# USB_Communication.net
KiCad netlist of a schematic drawn in Altium Designer
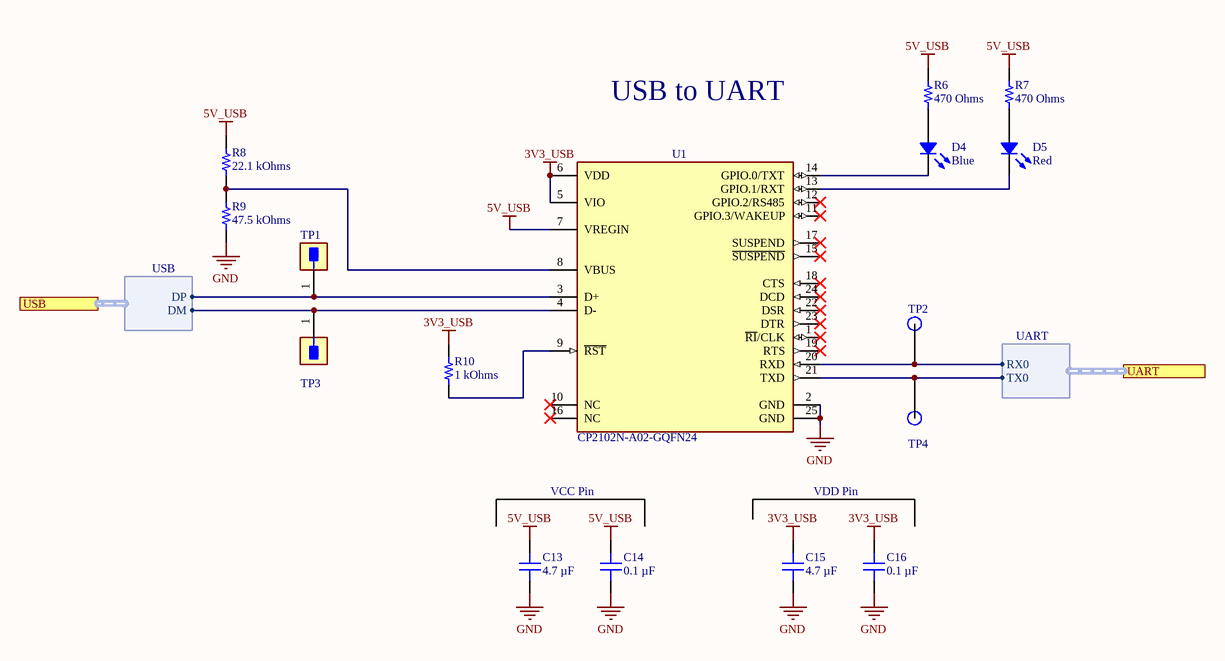
[diagram p0: USB Communication.SchDoc]

(export (version "E")
  (design (tool "Eeschema 10.0.6"))
  (components
    (comp (ref "C13")
      (value "4.7 µF")
      (footprint "CAP 0603_1608")
      (description "CAP CER 4.7UF 10V X5R 0603")
      (fields
        (field (name "PART NUMBER") "CL10A475KP8NNNC")
        (field (name "MANUFACTURER") "Samsung Electro-Mechanics")
      )
      (libsource (lib "Celestial Altium Library - altium_library") (part "Capacitor"))
    )
    (comp (ref "C14")
      (value "0.1 µF")
      (footprint "CAP 0603_1608")
      (description "CAP CER 0.1UF 50V X7R 0603")
      (fields (field (name "PART NUMBER") "C0603C104K5RAC7411") (field (name "MANUFACTURER") "KEMET"))
      (libsource (lib "Celestial Altium Library - altium_library") (part "Capacitor"))
    )
    (comp (ref "C15")
      (value "4.7 µF")
      (footprint "CAP 0603_1608")
      (description "CAP CER 4.7UF 10V X5R 0603")
      (fields
        (field (name "PART NUMBER") "CL10A475KP8NNNC")
        (field (name "MANUFACTURER") "Samsung Electro-Mechanics")
      )
      (libsource (lib "Celestial Altium Library - altium_library") (part "Capacitor"))
    )
    (comp (ref "C16")
      (value "0.1 µF")
      (footprint "CAP 0603_1608")
      (description "CAP CER 0.1UF 50V X7R 0603")
      (fields (field (name "PART NUMBER") "C0603C104K5RAC7411") (field (name "MANUFACTURER") "KEMET"))
      (libsource (lib "Celestial Altium Library - altium_library") (part "Capacitor"))
    )
    (comp (ref "D4")
      (value "Blue")
      (footprint "LED 0603_1608 BLUE")
      (description "LED BLUE CLEAR CHIP SMD")
      (fields (field (name "PART NUMBER") "LTST-C193TBKT-5A") (field (name "MANUFACTURER") "Lite-On Inc."))
      (libsource (lib "Celestial Altium Library - altium_library") (part "LED"))
    )
    (comp (ref "D5")
      (value "Red")
      (footprint "LED 0603_1608 RED")
      (description "LED RED CLEAR CHIP SMD")
      (fields (field (name "PART NUMBER") "LTST-C190KAKT") (field (name "MANUFACTURER") "Lite-On Inc."))
      (libsource (lib "Celestial Altium Library - altium_library") (part "LED"))
    )
    (comp (ref "R6")
      (value "470 Ohms")
      (footprint "RES 0603_1608")
      (description "RES SMD 470 OHM 1% 1/10W 0603")
      (fields
        (field (name "PART NUMBER") "ERJ-3EKF4700V")
        (field (name "MANUFACTURER") "Panasonic Electronic Components")
      )
      (libsource (lib "Celestial Altium Library - altium_library") (part "Resistor"))
    )
    (comp (ref "R7")
      (value "470 Ohms")
      (footprint "RES 0603_1608")
      (description "RES SMD 470 OHM 1% 1/10W 0603")
      (fields
        (field (name "PART NUMBER") "ERJ-3EKF4700V")
        (field (name "MANUFACTURER") "Panasonic Electronic Components")
      )
      (libsource (lib "Celestial Altium Library - altium_library") (part "Resistor"))
    )
    (comp (ref "R8")
      (value "22.1 kOhms")
      (footprint "RES 0603_1608")
      (description "RES 22.1K OHM 1% 1/10W 0603")
      (fields
        (field (name "PART NUMBER") "RMCF0603FT22K1")
        (field (name "MANUFACTURER") "Stackpole Electronics Inc")
      )
      (libsource (lib "Celestial Altium Library - altium_library") (part "Resistor"))
    )
    (comp (ref "R9")
      (value "47.5 kOhms")
      (footprint "RES 0603_1608")
      (description "RES 47.5K OHM 1% 1/10W 0603")
      (fields
        (field (name "PART NUMBER") "RMCF0603FT47K5")
        (field (name "MANUFACTURER") "Stackpole Electronics Inc")
      )
      (libsource (lib "Celestial Altium Library - altium_library") (part "Resistor"))
    )
    (comp (ref "R10")
      (value "1 kOhms")
      (footprint "RES 0603_1608")
      (description "RES SMD 1K OHM 1% 1/10W 0603")
      (fields (field (name "PART NUMBER") "CRCW06031K00FKEB") (field (name "MANUFACTURER") "Vishay Dale"))
      (libsource (lib "Celestial Altium Library - altium_library") (part "Resistor"))
    )
    (comp (ref "TP1")
      (value "S2751-46R")
      (footprint "FP-S2751-46R-MFG")
      (description "Conn Test Point 1 POS Solder ST SMD 1 Port T/R")
      (libsource (lib "Americas- Environmental Engineering Club- University of Victoria") (part "dd45045ce8184df9e99e12baf3f412c"))
    )
    (comp (ref "TP2")
      (value "1.5mm Test Point")
      (footprint "1mm Test Point-Footprint-1")
      (description "1.5mm Test Point 0.75mm hole size")
      (libsource (lib "Americas- Environmental Engineering Club- University of Victoria") (part "1mm Test Point-Symbol-1"))
    )
    (comp (ref "TP3")
      (value "S2751-46R")
      (footprint "FP-S2751-46R-MFG")
      (description "Conn Test Point 1 POS Solder ST SMD 1 Port T/R")
      (libsource (lib "") (part "dd45045ce8184df9e99e12baf3f412c_1"))
    )
    (comp (ref "TP4")
      (value "1.5mm Test Point")
      (footprint "1mm Test Point-Footprint-1")
      (description "1.5mm Test Point 0.75mm hole size")
      (libsource (lib "Americas- Environmental Engineering Club- University of Victoria") (part "1mm Test Point-Symbol-1"))
    )
    (comp (ref "U1")
      (value "CP2102N-A02-GQFN24")
      (footprint "FP-CP2102N-A02-GQFN24-MFG")
      (description "IC USB TO UART BRIDGE QFN24")
      (libsource (lib "Altium Content Vault") (part "132705adcabca70c0fc25feb25b66a0"))
    )
  )
  (nets
    (net (code "5") (name "3V3_USB") (class "Default")
      (node (ref "C15") (pin "2") (pinfunction "2_2") (pintype "passive"))
      (node (ref "C16") (pin "2") (pinfunction "2_2") (pintype "passive"))
      (node (ref "R10") (pin "2") (pinfunction "2_2") (pintype "passive"))
      (node (ref "U1") (pin "5") (pinfunction "VIO_5") (pintype "power_in"))
      (node (ref "U1") (pin "6") (pinfunction "VDD_6") (pintype "power_in"))
    )
    (net (code "6") (name "5V_USB") (class "Default")
      (node (ref "C13") (pin "2") (pinfunction "2_2") (pintype "passive"))
      (node (ref "C14") (pin "2") (pinfunction "2_2") (pintype "passive"))
      (node (ref "R6") (pin "1") (pinfunction "1_1") (pintype "passive"))
      (node (ref "R7") (pin "1") (pinfunction "1_1") (pintype "passive"))
      (node (ref "R8") (pin "2") (pinfunction "2_2") (pintype "passive"))
      (node (ref "U1") (pin "7") (pinfunction "VREGIN_7") (pintype "power_in"))
    )
    (net (code "7") (name "GND") (class "Default")
      (node (ref "C13") (pin "1") (pinfunction "1_1") (pintype "passive"))
      (node (ref "C14") (pin "1") (pinfunction "1_1") (pintype "passive"))
      (node (ref "C15") (pin "1") (pinfunction "1_1") (pintype "passive"))
      (node (ref "C16") (pin "1") (pinfunction "1_1") (pintype "passive"))
      (node (ref "R9") (pin "1") (pinfunction "1_1") (pintype "passive"))
      (node (ref "U1") (pin "2") (pinfunction "GND_2") (pintype "power_in"))
      (node (ref "U1") (pin "25") (pinfunction "GND_25") (pintype "power_in"))
    )
    (net (code "8") (name "Net-(D4-Pad1)") (class "Default")
      (node (ref "D4") (pin "1") (pinfunction "1_1") (pintype "passive"))
      (node (ref "R6") (pin "2") (pinfunction "2_2") (pintype "passive"))
    )
    (net (code "9") (name "Net-(D5-Pad1)") (class "Default")
      (node (ref "D5") (pin "1") (pinfunction "1_1") (pintype "passive"))
      (node (ref "R7") (pin "2") (pinfunction "2_2") (pintype "passive"))
    )
    (net (code "10") (name "Net-(U1-D+)") (class "Default")
      (node (ref "TP1") (pin "1") (pinfunction "1_1") (pintype "passive"))
      (node (ref "U1") (pin "3") (pinfunction "D+_3") (pintype "passive"))
    )
    (net (code "11") (name "Net-(U1-D-)") (class "Default")
      (node (ref "TP3") (pin "1") (pinfunction "1_1") (pintype "passive"))
      (node (ref "U1") (pin "4") (pinfunction "D-_4") (pintype "passive"))
    )
    (net (code "12") (name "Net-(U1-GPIO.0{slash}TXT)") (class "Default")
      (node (ref "D4") (pin "2") (pinfunction "2_2") (pintype "passive"))
      (node (ref "U1") (pin "14") (pinfunction "GPIO.0/TXT_14") (pintype "bidirectional"))
    )
    (net (code "13") (name "Net-(U1-GPIO.1{slash}RXT)") (class "Default")
      (node (ref "D5") (pin "2") (pinfunction "2_2") (pintype "passive"))
      (node (ref "U1") (pin "13") (pinfunction "GPIO.1/RXT_13") (pintype "bidirectional"))
    )
    (net (code "14") (name "Net-(U1-RXD)") (class "Default")
      (node (ref "TP2") (pin "1") (pinfunction "1_1") (pintype "passive"))
      (node (ref "U1") (pin "20") (pinfunction "RXD_20") (pintype "input"))
    )
    (net (code "15") (name "Net-(U1-TXD)") (class "Default")
      (node (ref "TP4") (pin "1") (pinfunction "1_1") (pintype "passive"))
      (node (ref "U1") (pin "21") (pinfunction "TXD_21") (pintype "output"))
    )
    (net (code "16") (name "Net-(U1-VBUS)") (class "Default")
      (node (ref "R8") (pin "1") (pinfunction "1_1") (pintype "passive"))
      (node (ref "R9") (pin "2") (pinfunction "2_2") (pintype "passive"))
      (node (ref "U1") (pin "8") (pinfunction "VBUS_8") (pintype "power_in"))
    )
    (net (code "17") (name "Net-(U1-~{RST})") (class "Default")
      (node (ref "R10") (pin "1") (pinfunction "1_1") (pintype "passive"))
      (node (ref "U1") (pin "9") (pinfunction "~{RST}_9") (pintype "input"))
    )
    (net (code "18") (name "unconnected-(U1-CTS-Pad18)") (class "Default")
      (node (ref "U1") (pin "18") (pinfunction "CTS_18") (pintype "input+no_connect"))
    )
    (net (code "19") (name "unconnected-(U1-DCD-Pad24)") (class "Default")
      (node (ref "U1") (pin "24") (pinfunction "DCD_24") (pintype "input+no_connect"))
    )
    (net (code "20") (name "unconnected-(U1-DSR-Pad22)") (class "Default")
      (node (ref "U1") (pin "22") (pinfunction "DSR_22") (pintype "input+no_connect"))
    )
    (net (code "21") (name "unconnected-(U1-DTR-Pad23)") (class "Default")
      (node (ref "U1") (pin "23") (pinfunction "DTR_23") (pintype "output+no_connect"))
    )
    (net (code "22") (name "unconnected-(U1-GPIO.2{slash}RS485-Pad12)") (class "Default")
      (node (ref "U1") (pin "12") (pinfunction "GPIO.2/RS485_12") (pintype "bidirectional+no_connect"))
    )
    (net (code "23") (name "unconnected-(U1-GPIO.3{slash}WAKEUP-Pad11)") (class "Default")
      (node (ref "U1") (pin "11") (pinfunction "GPIO.3/WAKEUP_11") (pintype "bidirectional+no_connect"))
    )
    (net (code "24") (name "unconnected-(U1-NC-Pad10)") (class "Default")
      (node (ref "U1") (pin "10") (pinfunction "NC_10") (pintype "passive+no_connect"))
    )
    (net (code "25") (name "unconnected-(U1-NC-Pad16)") (class "Default")
      (node (ref "U1") (pin "16") (pinfunction "NC_16") (pintype "passive+no_connect"))
    )
    (net (code "26") (name "unconnected-(U1-RTS-Pad19)") (class "Default")
      (node (ref "U1") (pin "19") (pinfunction "RTS_19") (pintype "output+no_connect"))
    )
    (net (code "27") (name "unconnected-(U1-SUSPEND-Pad17)") (class "Default")
      (node (ref "U1") (pin "17") (pinfunction "SUSPEND_17") (pintype "output+no_connect"))
    )
    (net (code "28") (name "unconnected-(U1-~{RI}{slash}CLK-Pad1)") (class "Default")
      (node (ref "U1") (pin "1") (pinfunction "~{RI}/CLK_1") (pintype "bidirectional+no_connect"))
    )
    (net (code "29") (name "unconnected-(U1-~{SUSPEND}-Pad15)") (class "Default")
      (node (ref "U1") (pin "15") (pinfunction "~{SUSPEND}_15") (pintype "output+no_connect"))
    )
  )
)
